# uv-dosimeter-guva-op-amp-mk-1_0.net
KiCad netlist of a schematic drawn in EAGLE
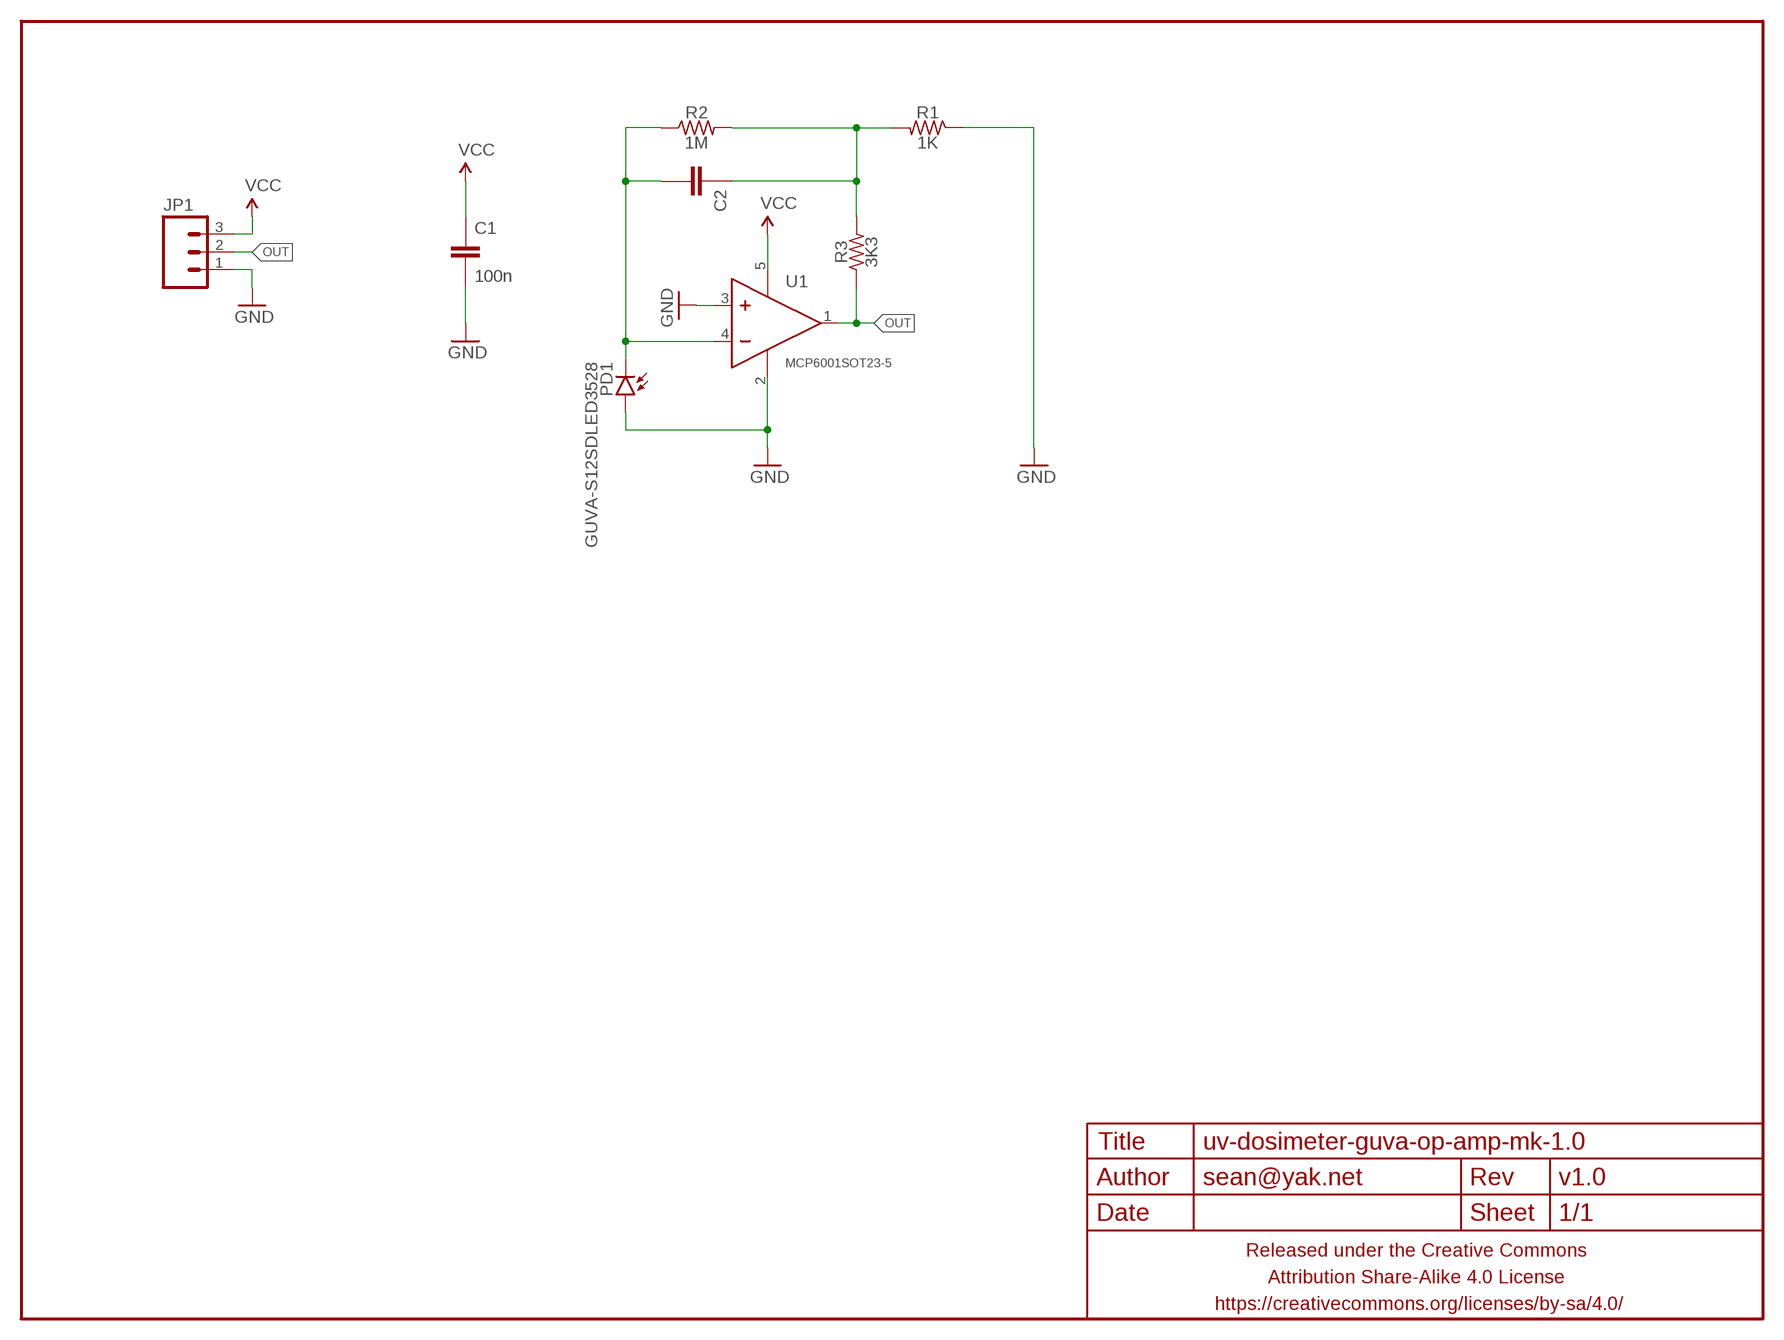
[diagram p0: schematic, sheet 1]

(export (version "E")
  (design (tool "Eeschema 10.0.6"))
  (components
    (comp (ref "C1")
      (value "100n")
      (footprint "eagle-import:C0603")
      (libsource (lib "eagle-import") (part "CAPACITOR-CERAMICC0603"))
    )
    (comp (ref "C2")
      (value "CAPACITOR-CERAMICC0603")
      (footprint "eagle-import:C0603")
      (libsource (lib "eagle-import") (part "CAPACITOR-CERAMICC0603"))
    )
    (comp (ref "FRAME1")
      (value "FRAME-LETTERNO_PACKAGE")
      (footprint "eagle-import:DUMMY")
      (fields (field (name "DESIGNER") "sean@yak.net") (field (name "VERSION") "v1.0"))
      (libsource (lib "eagle-import") (part "FRAME-LETTERNO_PACKAGE"))
    )
    (comp (ref "JP1")
      (value "M03PTH-CENTERED")
      (footprint "eagle-import:1X03-CENTERED")
      (libsource (lib "eagle-import") (part "M03PTH-CENTERED"))
    )
    (comp (ref "PD1")
      (value "GUVA-S12SDLED3528")
      (footprint "eagle-import:LED3528")
      (libsource (lib "eagle-import") (part "GUVA-S12SDLED3528"))
    )
    (comp (ref "R1")
      (value "1K")
      (footprint "eagle-import:R0603")
      (libsource (lib "eagle-import") (part "RESISTORR0603"))
    )
    (comp (ref "R2")
      (value "1M")
      (footprint "eagle-import:R0603")
      (libsource (lib "eagle-import") (part "RESISTORR0603"))
    )
    (comp (ref "R3")
      (value "3K3")
      (footprint "eagle-import:R0603")
      (libsource (lib "eagle-import") (part "RESISTORR0603"))
    )
    (comp (ref "U1")
      (value "MCP6001SOT23-5")
      (footprint "eagle-import:SOT23-5")
      (libsource (lib "eagle-import") (part "MCP6001SOT23-5"))
    )
  )
  (nets
    (net (code "1") (name "GND") (class "Default")
      (node (ref "C1") (pin "2") (pinfunction "2_2") (pintype "passive"))
      (node (ref "JP1") (pin "1") (pinfunction "1_1") (pintype "passive"))
      (node (ref "PD1") (pin "A") (pinfunction "A_A") (pintype "passive"))
      (node (ref "R1") (pin "1") (pinfunction "1_1") (pintype "passive"))
      (node (ref "U1") (pin "2") (pinfunction "V-_2") (pintype "power_in"))
      (node (ref "U1") (pin "3") (pinfunction "IN+_3") (pintype "input"))
    )
    (net (code "2") (name "Net-(C2-Pad1)") (class "Default")
      (node (ref "C2") (pin "1") (pinfunction "1_1") (pintype "passive"))
      (node (ref "R1") (pin "2") (pinfunction "2_2") (pintype "passive"))
      (node (ref "R2") (pin "2") (pinfunction "2_2") (pintype "passive"))
      (node (ref "R3") (pin "2") (pinfunction "2_2") (pintype "passive"))
    )
    (net (code "3") (name "Net-(PD1-C)") (class "Default")
      (node (ref "C2") (pin "2") (pinfunction "2_2") (pintype "passive"))
      (node (ref "PD1") (pin "K") (pinfunction "C_K") (pintype "passive"))
      (node (ref "R2") (pin "1") (pinfunction "1_1") (pintype "passive"))
      (node (ref "U1") (pin "4") (pinfunction "IN-_4") (pintype "input"))
    )
    (net (code "4") (name "OUT") (class "Default")
      (node (ref "JP1") (pin "2") (pinfunction "2_2") (pintype "passive"))
      (node (ref "R3") (pin "1") (pinfunction "1_1") (pintype "passive"))
      (node (ref "U1") (pin "1") (pinfunction "OUT_1") (pintype "output"))
    )
    (net (code "5") (name "VCC") (class "Default")
      (node (ref "C1") (pin "1") (pinfunction "1_1") (pintype "passive"))
      (node (ref "JP1") (pin "3") (pinfunction "3_3") (pintype "passive"))
      (node (ref "U1") (pin "5") (pinfunction "V+_5") (pintype "power_in"))
    )
  )
)
